# schematic.net
KiCad netlist of a schematic drawn in EAGLE
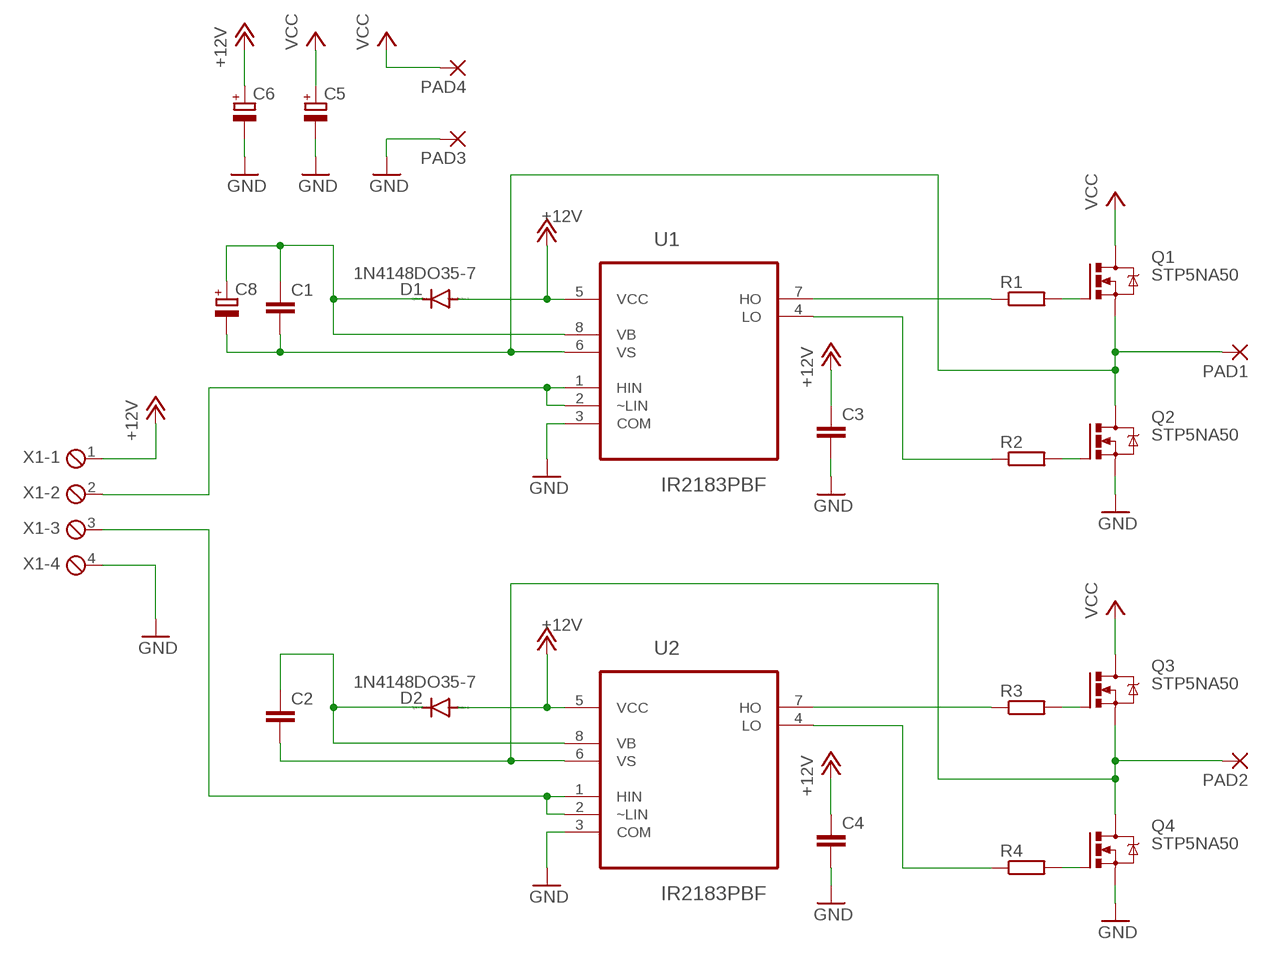
[diagram p0: schematic, sheet 1]

(export (version "E")
  (design (tool "Eeschema 10.0.6"))
  (components
    (comp (ref "C1")
      (value "C-EU050-024X044")
      (footprint "eagle-import:C050-024X044")
      (libsource (lib "eagle-import") (part "C-EU050-024X044"))
    )
    (comp (ref "C2")
      (value "C-EU050-024X044")
      (footprint "eagle-import:C050-024X044")
      (libsource (lib "eagle-import") (part "C-EU050-024X044"))
    )
    (comp (ref "C3")
      (value "C-EU050-024X044")
      (footprint "eagle-import:C050-024X044")
      (libsource (lib "eagle-import") (part "C-EU050-024X044"))
    )
    (comp (ref "C4")
      (value "C-EU050-024X044")
      (footprint "eagle-import:C050-024X044")
      (libsource (lib "eagle-import") (part "C-EU050-024X044"))
    )
    (comp (ref "C5")
      (value "CPOL-EUE5-10.5")
      (footprint "eagle-import:E5-10,5")
      (libsource (lib "eagle-import") (part "CPOL-EUE5-10.5"))
    )
    (comp (ref "C6")
      (value "CPOL-EUE2.5-6")
      (footprint "eagle-import:E2,5-6")
      (libsource (lib "eagle-import") (part "CPOL-EUE2.5-6"))
    )
    (comp (ref "C8")
      (value "CPOL-EUE2.5-6")
      (footprint "eagle-import:E2,5-6")
      (libsource (lib "eagle-import") (part "CPOL-EUE2.5-6"))
    )
    (comp (ref "D1")
      (value "1N4148DO35-7")
      (footprint "eagle-import:DO35-7")
      (libsource (lib "eagle-import") (part "1N4148DO35-7"))
    )
    (comp (ref "D2")
      (value "1N4148DO35-7")
      (footprint "eagle-import:DO35-7")
      (libsource (lib "eagle-import") (part "1N4148DO35-7"))
    )
    (comp (ref "PAD1")
      (value "3,81/1,4")
      (footprint "eagle-import:3,81_1,4")
      (libsource (lib "eagle-import") (part "3,81/1,4"))
    )
    (comp (ref "PAD2")
      (value "3,81/1,4")
      (footprint "eagle-import:3,81_1,4")
      (libsource (lib "eagle-import") (part "3,81/1,4"))
    )
    (comp (ref "PAD3")
      (value "3,81/1,4")
      (footprint "eagle-import:3,81_1,4")
      (libsource (lib "eagle-import") (part "3,81/1,4"))
    )
    (comp (ref "PAD4")
      (value "3,81/1,4")
      (footprint "eagle-import:3,81_1,4")
      (libsource (lib "eagle-import") (part "3,81/1,4"))
    )
    (comp (ref "Q1")
      (value "STP5NA50")
      (footprint "eagle-import:TO220BV")
      (libsource (lib "eagle-import") (part "STP5NA50"))
    )
    (comp (ref "Q2")
      (value "STP5NA50")
      (footprint "eagle-import:TO220BV")
      (libsource (lib "eagle-import") (part "STP5NA50"))
    )
    (comp (ref "Q3")
      (value "STP5NA50")
      (footprint "eagle-import:TO220BV")
      (libsource (lib "eagle-import") (part "STP5NA50"))
    )
    (comp (ref "Q4")
      (value "STP5NA50")
      (footprint "eagle-import:TO220BV")
      (libsource (lib "eagle-import") (part "STP5NA50"))
    )
    (comp (ref "R1")
      (value "R-EU_0204/7")
      (footprint "eagle-import:0204_7")
      (libsource (lib "eagle-import") (part "R-EU_0204/7"))
    )
    (comp (ref "R2")
      (value "R-EU_0204/7")
      (footprint "eagle-import:0204_7")
      (libsource (lib "eagle-import") (part "R-EU_0204/7"))
    )
    (comp (ref "R3")
      (value "R-EU_0204/7")
      (footprint "eagle-import:0204_7")
      (libsource (lib "eagle-import") (part "R-EU_0204/7"))
    )
    (comp (ref "R4")
      (value "R-EU_0204/7")
      (footprint "eagle-import:0204_7")
      (libsource (lib "eagle-import") (part "R-EU_0204/7"))
    )
    (comp (ref "U1")
      (value "IR2183PBF")
      (footprint "eagle-import:DIP254P762X533-8")
      (fields (field (name "MF") "Infineon Technologies"))
      (libsource (lib "eagle-import") (part "IR2183PBF"))
    )
    (comp (ref "U2")
      (value "IR2183PBF")
      (footprint "eagle-import:DIP254P762X533-8")
      (fields (field (name "MF") "Infineon Technologies"))
      (libsource (lib "eagle-import") (part "IR2183PBF"))
    )
    (comp (ref "X1")
      (value "MPT4")
      (footprint "eagle-import:4POL254")
      (libsource (lib "eagle-import") (part "MPT4"))
    )
  )
  (nets
    (net (code "1") (name "+12V") (class "Default")
      (node (ref "C3") (pin "1") (pinfunction "1_1") (pintype "passive"))
      (node (ref "C4") (pin "1") (pinfunction "1_1") (pintype "passive"))
      (node (ref "C6") (pin "+") (pinfunction "+_+") (pintype "passive"))
      (node (ref "D1") (pin "A") (pinfunction "A_A") (pintype "passive"))
      (node (ref "D2") (pin "A") (pinfunction "A_A") (pintype "passive"))
      (node (ref "U1") (pin "5") (pinfunction "VCC_5") (pintype "power_in"))
      (node (ref "U2") (pin "5") (pinfunction "VCC_5") (pintype "power_in"))
      (node (ref "X1") (pin "1") (pinfunction "1_1") (pintype "passive"))
    )
    (net (code "2") (name "GND") (class "Default")
      (node (ref "C3") (pin "2") (pinfunction "2_2") (pintype "passive"))
      (node (ref "C4") (pin "2") (pinfunction "2_2") (pintype "passive"))
      (node (ref "C5") (pin "-") (pinfunction "-_-") (pintype "passive"))
      (node (ref "C6") (pin "-") (pinfunction "-_-") (pintype "passive"))
      (node (ref "PAD3") (pin "1") (pinfunction "P_1") (pintype "passive"))
      (node (ref "Q2") (pin "S") (pinfunction "S_S") (pintype "passive"))
      (node (ref "Q4") (pin "S") (pinfunction "S_S") (pintype "passive"))
      (node (ref "U1") (pin "3") (pinfunction "COM_3") (pintype "input"))
      (node (ref "U2") (pin "3") (pinfunction "COM_3") (pintype "input"))
      (node (ref "X1") (pin "4") (pinfunction "1_4") (pintype "passive"))
    )
    (net (code "3") (name "Net-(PAD1-P)") (class "Default")
      (node (ref "C1") (pin "2") (pinfunction "2_2") (pintype "passive"))
      (node (ref "C8") (pin "-") (pinfunction "-_-") (pintype "passive"))
      (node (ref "PAD1") (pin "1") (pinfunction "P_1") (pintype "passive"))
      (node (ref "Q1") (pin "S") (pinfunction "S_S") (pintype "passive"))
      (node (ref "Q2") (pin "D") (pinfunction "D_D") (pintype "passive"))
      (node (ref "U1") (pin "6") (pinfunction "VS_6") (pintype "power_in"))
    )
    (net (code "4") (name "Net-(PAD2-P)") (class "Default")
      (node (ref "C2") (pin "2") (pinfunction "2_2") (pintype "passive"))
      (node (ref "PAD2") (pin "1") (pinfunction "P_1") (pintype "passive"))
      (node (ref "Q3") (pin "S") (pinfunction "S_S") (pintype "passive"))
      (node (ref "Q4") (pin "D") (pinfunction "D_D") (pintype "passive"))
      (node (ref "U2") (pin "6") (pinfunction "VS_6") (pintype "power_in"))
    )
    (net (code "5") (name "Net-(Q1-PadG)") (class "Default")
      (node (ref "Q1") (pin "G") (pinfunction "G_G") (pintype "passive"))
      (node (ref "R1") (pin "2") (pinfunction "2_2") (pintype "passive"))
    )
    (net (code "6") (name "Net-(Q2-PadG)") (class "Default")
      (node (ref "Q2") (pin "G") (pinfunction "G_G") (pintype "passive"))
      (node (ref "R2") (pin "2") (pinfunction "2_2") (pintype "passive"))
    )
    (net (code "7") (name "Net-(Q3-PadG)") (class "Default")
      (node (ref "Q3") (pin "G") (pinfunction "G_G") (pintype "passive"))
      (node (ref "R3") (pin "2") (pinfunction "2_2") (pintype "passive"))
    )
    (net (code "8") (name "Net-(Q4-PadG)") (class "Default")
      (node (ref "Q4") (pin "G") (pinfunction "G_G") (pintype "passive"))
      (node (ref "R4") (pin "2") (pinfunction "2_2") (pintype "passive"))
    )
    (net (code "9") (name "Net-(U1-HIN)") (class "Default")
      (node (ref "U1") (pin "1") (pinfunction "HIN_1") (pintype "input"))
      (node (ref "U1") (pin "2") (pinfunction "~{LIN}_2") (pintype "input"))
      (node (ref "X1") (pin "2") (pinfunction "1_2") (pintype "passive"))
    )
    (net (code "10") (name "Net-(U1-HO)") (class "Default")
      (node (ref "R1") (pin "1") (pinfunction "1_1") (pintype "passive"))
      (node (ref "U1") (pin "7") (pinfunction "HO_7") (pintype "output"))
    )
    (net (code "11") (name "Net-(U1-LO)") (class "Default")
      (node (ref "R2") (pin "1") (pinfunction "1_1") (pintype "passive"))
      (node (ref "U1") (pin "4") (pinfunction "LO_4") (pintype "output"))
    )
    (net (code "12") (name "Net-(U1-VB)") (class "Default")
      (node (ref "C1") (pin "1") (pinfunction "1_1") (pintype "passive"))
      (node (ref "C8") (pin "+") (pinfunction "+_+") (pintype "passive"))
      (node (ref "D1") (pin "C") (pinfunction "C_C") (pintype "passive"))
      (node (ref "U1") (pin "8") (pinfunction "VB_8") (pintype "power_in"))
    )
    (net (code "13") (name "Net-(U2-HIN)") (class "Default")
      (node (ref "U2") (pin "1") (pinfunction "HIN_1") (pintype "input"))
      (node (ref "U2") (pin "2") (pinfunction "~{LIN}_2") (pintype "input"))
      (node (ref "X1") (pin "3") (pinfunction "1_3") (pintype "passive"))
    )
    (net (code "14") (name "Net-(U2-HO)") (class "Default")
      (node (ref "R3") (pin "1") (pinfunction "1_1") (pintype "passive"))
      (node (ref "U2") (pin "7") (pinfunction "HO_7") (pintype "output"))
    )
    (net (code "15") (name "Net-(U2-LO)") (class "Default")
      (node (ref "R4") (pin "1") (pinfunction "1_1") (pintype "passive"))
      (node (ref "U2") (pin "4") (pinfunction "LO_4") (pintype "output"))
    )
    (net (code "16") (name "Net-(U2-VB)") (class "Default")
      (node (ref "C2") (pin "1") (pinfunction "1_1") (pintype "passive"))
      (node (ref "D2") (pin "C") (pinfunction "C_C") (pintype "passive"))
      (node (ref "U2") (pin "8") (pinfunction "VB_8") (pintype "power_in"))
    )
    (net (code "17") (name "VCC") (class "Default")
      (node (ref "C5") (pin "+") (pinfunction "+_+") (pintype "passive"))
      (node (ref "PAD4") (pin "1") (pinfunction "P_1") (pintype "passive"))
      (node (ref "Q1") (pin "D") (pinfunction "D_D") (pintype "passive"))
      (node (ref "Q3") (pin "D") (pinfunction "D_D") (pintype "passive"))
    )
  )
)
